# DownLink_ver1.net
KiCad netlist of a schematic drawn in EAGLE
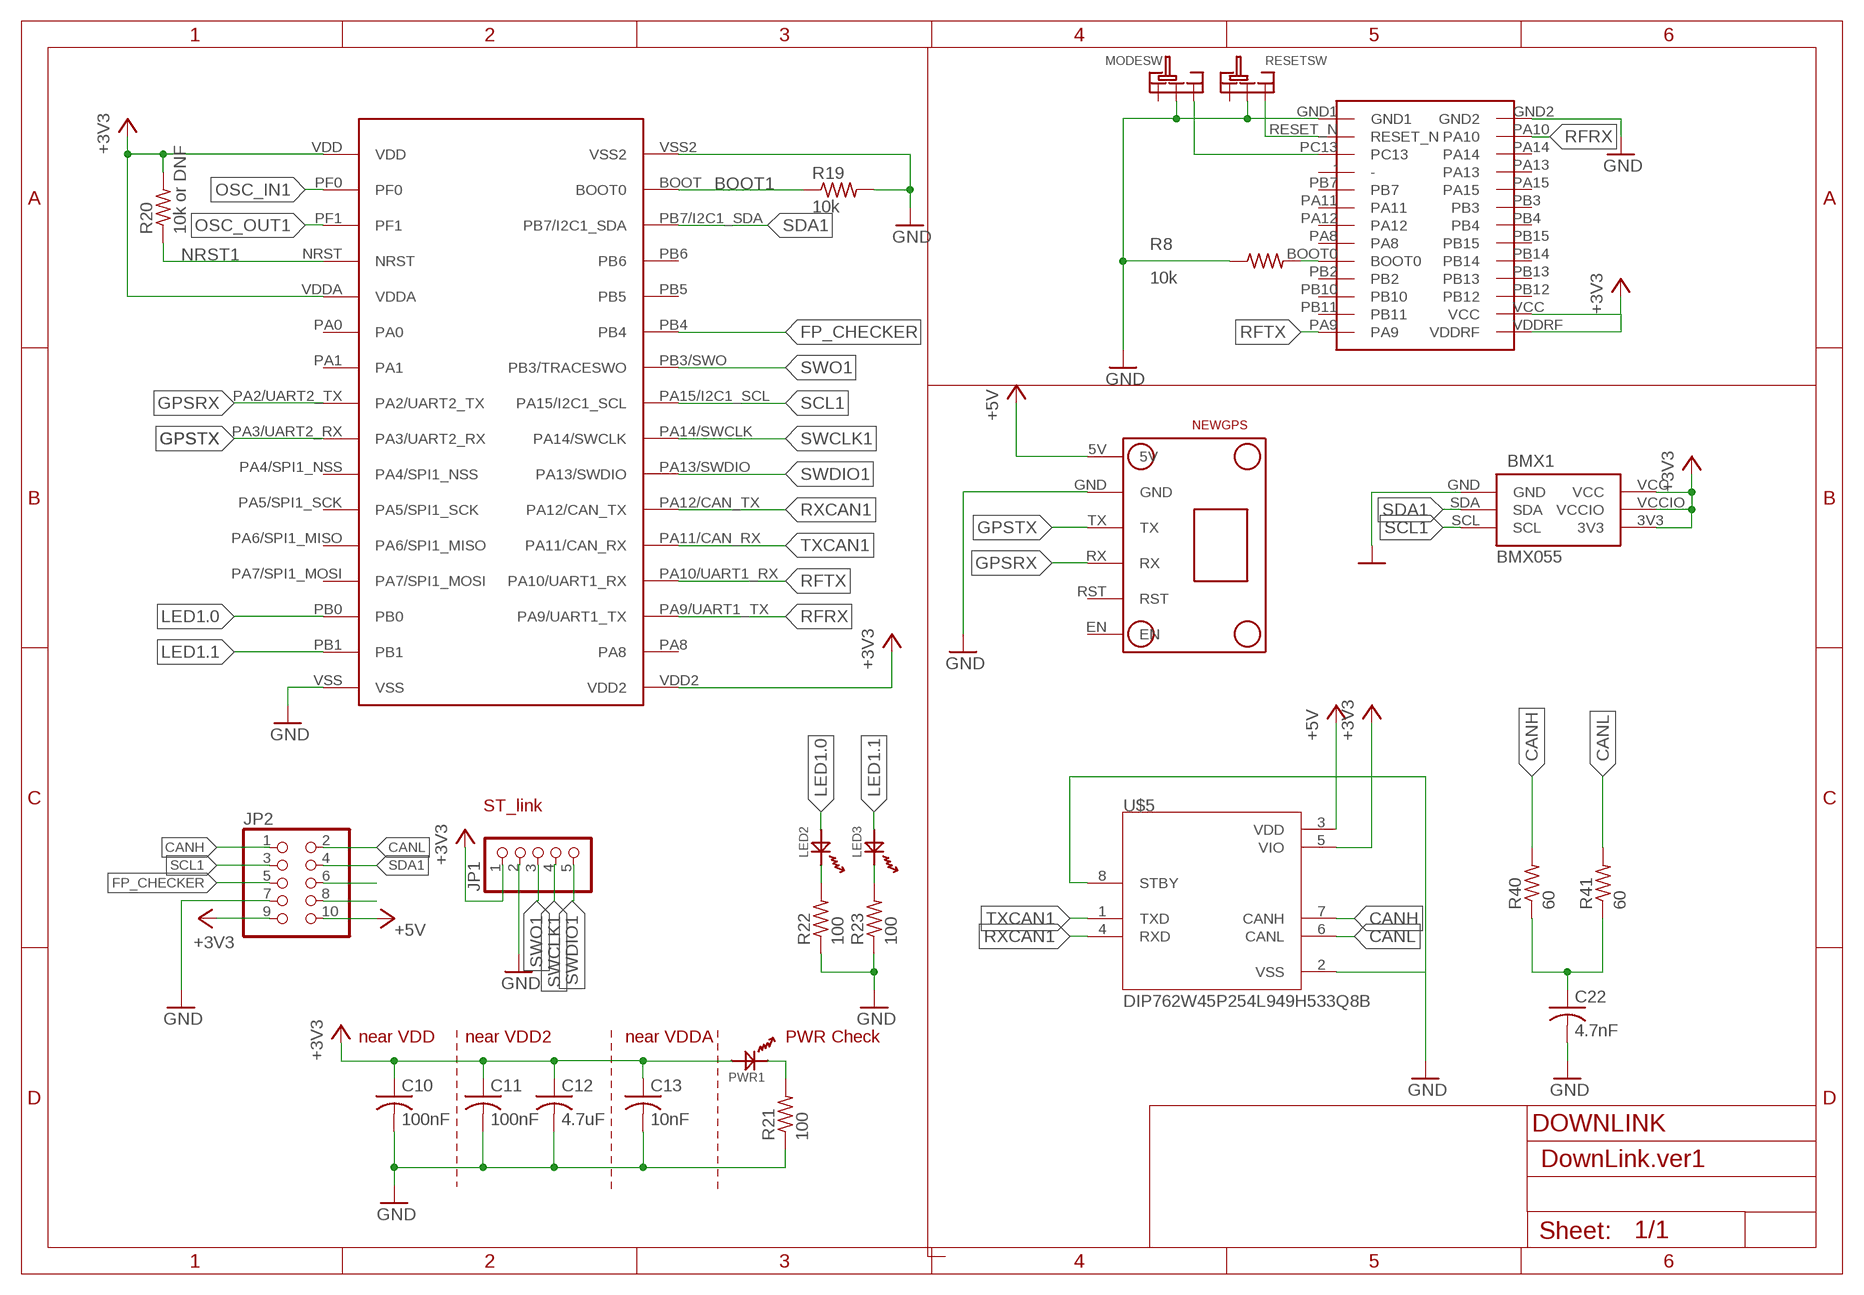
[diagram p0: schematic, sheet 1]

(export (version "E")
  (design (tool "Eeschema 10.0.6"))
  (components
    (comp (ref "BMX1")
      (value "BMX055")
      (footprint "eagle-import:BMX055")
      (libsource (lib "eagle-import") (part "BMX055"))
    )
    (comp (ref "C10")
      (value "100nF")
      (footprint "eagle-import:C1608")
      (libsource (lib "eagle-import") (part "C-USC1608"))
    )
    (comp (ref "C11")
      (value "100nF")
      (footprint "eagle-import:C1608")
      (libsource (lib "eagle-import") (part "C-USC1608"))
    )
    (comp (ref "C12")
      (value "4.7uF")
      (footprint "eagle-import:C1608")
      (libsource (lib "eagle-import") (part "C-USC1608"))
    )
    (comp (ref "C13")
      (value "10nF")
      (footprint "eagle-import:C1608")
      (libsource (lib "eagle-import") (part "C-USC1608"))
    )
    (comp (ref "C22")
      (value "4.7nF")
      (footprint "eagle-import:C0603")
      (libsource (lib "eagle-import") (part "C-USC0603"))
    )
    (comp (ref "JP1")
      (value "PINHD-1X5/90")
      (footprint "eagle-import:1X05_90")
      (libsource (lib "eagle-import") (part "PINHD-1X5/90"))
    )
    (comp (ref "JP2")
      (value "PINHD-2X5/90")
      (footprint "eagle-import:2X05_90")
      (libsource (lib "eagle-import") (part "PINHD-2X5/90"))
    )
    (comp (ref "LED2")
      (value "OSXX1608C1A")
      (footprint "eagle-import:OSXX1608C1A")
      (libsource (lib "eagle-import") (part "OSXX1608C1A"))
    )
    (comp (ref "LED3")
      (value "OSXX1608C1A")
      (footprint "eagle-import:OSXX1608C1A")
      (libsource (lib "eagle-import") (part "OSXX1608C1A"))
    )
    (comp (ref "MODESW")
      (value "SRIDE_SWITCH")
      (footprint "eagle-import:SRIDE_SWITCH")
      (libsource (lib "eagle-import") (part "SRIDE_SWITCH"))
    )
    (comp (ref "PWR1")
      (value "OSXX1608C1A")
      (footprint "eagle-import:OSXX1608C1A")
      (libsource (lib "eagle-import") (part "OSXX1608C1A"))
    )
    (comp (ref "R8")
      (value "10k")
      (footprint "eagle-import:R0603")
      (libsource (lib "eagle-import") (part "R-US_R0603"))
    )
    (comp (ref "R19")
      (value "10k")
      (footprint "eagle-import:R0603")
      (libsource (lib "eagle-import") (part "R-US_R0603"))
    )
    (comp (ref "R20")
      (value "10k or DNF")
      (footprint "eagle-import:R0603")
      (libsource (lib "eagle-import") (part "R-US_R0603"))
    )
    (comp (ref "R21")
      (value "100")
      (footprint "eagle-import:R0603")
      (libsource (lib "eagle-import") (part "R-US_R0603"))
    )
    (comp (ref "R22")
      (value "100")
      (footprint "eagle-import:R0603")
      (libsource (lib "eagle-import") (part "R-US_R0603"))
    )
    (comp (ref "R23")
      (value "100")
      (footprint "eagle-import:R0603")
      (libsource (lib "eagle-import") (part "R-US_R0603"))
    )
    (comp (ref "R40")
      (value "60")
      (footprint "eagle-import:R0603")
      (libsource (lib "eagle-import") (part "R-US_R0603"))
    )
    (comp (ref "R41")
      (value "60")
      (footprint "eagle-import:R0603")
      (libsource (lib "eagle-import") (part "R-US_R0603"))
    )
    (comp (ref "RESETSW")
      (value "SRIDE_SWITCH")
      (footprint "eagle-import:SRIDE_SWITCH")
      (libsource (lib "eagle-import") (part "SRIDE_SWITCH"))
    )
    (comp (ref "STM1")
      (value "STM32F303K8")
      (footprint "eagle-import:STM32F303K8")
      (libsource (lib "eagle-import") (part "STM32F303K8"))
    )
    (comp (ref "U$1")
      (value "NEWGPS")
      (footprint "eagle-import:NEWGPS")
      (libsource (lib "eagle-import") (part "NEWGPS"))
    )
    (comp (ref "U$3")
      (value "RM-92A")
      (footprint "eagle-import:RM-92A")
      (libsource (lib "eagle-import") (part "RM-92A"))
    )
    (comp (ref "U$5")
      (value "DIP762W45P254L949H533Q8B")
      (footprint "eagle-import:DIP762W45P254L949H533Q8B")
      (libsource (lib "eagle-import") (part "DIP762W45P254L949H533Q8B"))
    )
  )
  (nets
    (net (code "1") (name "+3V3") (class "Default")
      (node (ref "BMX1") (pin "3V3") (pinfunction "3V3_3V3") (pintype "power_in"))
      (node (ref "BMX1") (pin "VCC") (pinfunction "VCC_VCC") (pintype "power_in"))
      (node (ref "BMX1") (pin "VCCIO") (pinfunction "VCCIO_VCCIO") (pintype "power_in"))
      (node (ref "C10") (pin "1") (pinfunction "1_1") (pintype "passive"))
      (node (ref "C11") (pin "1") (pinfunction "1_1") (pintype "passive"))
      (node (ref "C12") (pin "1") (pinfunction "1_1") (pintype "passive"))
      (node (ref "C13") (pin "1") (pinfunction "1_1") (pintype "passive"))
      (node (ref "JP1") (pin "1") (pinfunction "1_1") (pintype "passive"))
      (node (ref "JP2") (pin "9") (pinfunction "9_9") (pintype "passive"))
      (node (ref "PWR1") (pin "AN") (pinfunction "AN_AN") (pintype "bidirectional"))
      (node (ref "R20") (pin "2") (pinfunction "2_2") (pintype "passive"))
      (node (ref "STM1") (pin "VDD") (pinfunction "VDD_VDD") (pintype "power_in"))
      (node (ref "STM1") (pin "VDD2") (pinfunction "VDD2_VDD2") (pintype "power_in"))
      (node (ref "STM1") (pin "VDDA") (pinfunction "VDDA_VDDA") (pintype "power_in"))
      (node (ref "U$3") (pin "VCC") (pinfunction "VCC_VCC") (pintype "bidirectional"))
      (node (ref "U$3") (pin "VDDRF") (pinfunction "VDDRF_VDDRF") (pintype "bidirectional"))
      (node (ref "U$5") (pin "5") (pinfunction "VIO_5") (pintype "power_in"))
    )
    (net (code "2") (name "+5V") (class "Default")
      (node (ref "JP2") (pin "10") (pinfunction "10_10") (pintype "passive"))
      (node (ref "U$1") (pin "5V") (pinfunction "5V_5V") (pintype "bidirectional"))
      (node (ref "U$5") (pin "3") (pinfunction "VDD_3") (pintype "power_in"))
    )
    (net (code "3") (name "/BOOT1") (class "Default")
      (node (ref "R19") (pin "1") (pinfunction "1_1") (pintype "passive"))
      (node (ref "STM1") (pin "BOOT") (pinfunction "BOOT0_BOOT") (pintype "bidirectional"))
    )
    (net (code "4") (name "/NRST1") (class "Default")
      (node (ref "R20") (pin "1") (pinfunction "1_1") (pintype "passive"))
      (node (ref "STM1") (pin "NRST") (pinfunction "NRST_NRST") (pintype "bidirectional"))
    )
    (net (code "5") (name "CANH") (class "Default")
      (node (ref "JP2") (pin "1") (pinfunction "1_1") (pintype "passive"))
      (node (ref "R40") (pin "2") (pinfunction "2_2") (pintype "passive"))
      (node (ref "U$5") (pin "7") (pinfunction "CANH_7") (pintype "bidirectional"))
    )
    (net (code "6") (name "CANL") (class "Default")
      (node (ref "JP2") (pin "2") (pinfunction "2_2") (pintype "passive"))
      (node (ref "R41") (pin "2") (pinfunction "2_2") (pintype "passive"))
      (node (ref "U$5") (pin "6") (pinfunction "CANL_6") (pintype "bidirectional"))
    )
    (net (code "7") (name "FP_CHECKER") (class "Default")
      (node (ref "JP2") (pin "5") (pinfunction "5_5") (pintype "passive"))
      (node (ref "STM1") (pin "PB4") (pinfunction "PB4_PB4") (pintype "bidirectional"))
    )
    (net (code "8") (name "GND") (class "Default")
      (node (ref "BMX1") (pin "GND") (pinfunction "GND_GND") (pintype "power_in"))
      (node (ref "C10") (pin "2") (pinfunction "2_2") (pintype "passive"))
      (node (ref "C11") (pin "2") (pinfunction "2_2") (pintype "passive"))
      (node (ref "C12") (pin "2") (pinfunction "2_2") (pintype "passive"))
      (node (ref "C13") (pin "2") (pinfunction "2_2") (pintype "passive"))
      (node (ref "C22") (pin "2") (pinfunction "2_2") (pintype "passive"))
      (node (ref "JP1") (pin "2") (pinfunction "2_2") (pintype "passive"))
      (node (ref "JP2") (pin "7") (pinfunction "7_7") (pintype "passive"))
      (node (ref "MODESW") (pin "LR") (pinfunction "LR_LR") (pintype "bidirectional"))
      (node (ref "R19") (pin "2") (pinfunction "2_2") (pintype "passive"))
      (node (ref "R21") (pin "1") (pinfunction "1_1") (pintype "passive"))
      (node (ref "R22") (pin "1") (pinfunction "1_1") (pintype "passive"))
      (node (ref "R23") (pin "1") (pinfunction "1_1") (pintype "passive"))
      (node (ref "R8") (pin "1") (pinfunction "1_1") (pintype "passive"))
      (node (ref "RESETSW") (pin "LR") (pinfunction "LR_LR") (pintype "bidirectional"))
      (node (ref "STM1") (pin "VSS") (pinfunction "VSS_VSS") (pintype "power_in"))
      (node (ref "STM1") (pin "VSS2") (pinfunction "VSS2_VSS2") (pintype "power_in"))
      (node (ref "U$1") (pin "GND") (pinfunction "GND_GND") (pintype "bidirectional"))
      (node (ref "U$3") (pin "GND1") (pinfunction "GND1_GND1") (pintype "bidirectional"))
      (node (ref "U$3") (pin "GND2") (pinfunction "GND2_GND2") (pintype "bidirectional"))
      (node (ref "U$5") (pin "2") (pinfunction "VSS_2") (pintype "power_in"))
      (node (ref "U$5") (pin "8") (pinfunction "STBY_8") (pintype "input"))
    )
    (net (code "9") (name "GPSRX") (class "Default")
      (node (ref "STM1") (pin "PA2/UART2_TX") (pinfunction "PA2/UART2_TX_PA2/UART2_TX") (pintype "bidirectional"))
      (node (ref "U$1") (pin "RX") (pinfunction "RX_RX") (pintype "bidirectional"))
    )
    (net (code "10") (name "GPSTX") (class "Default")
      (node (ref "STM1") (pin "PA3/UART2_RX") (pinfunction "PA3/UART2_RX_PA3/UART2_RX") (pintype "bidirectional"))
      (node (ref "U$1") (pin "TX") (pinfunction "TX_TX") (pintype "bidirectional"))
    )
    (net (code "11") (name "LED1.0") (class "Default")
      (node (ref "LED2") (pin "AN") (pinfunction "AN_AN") (pintype "bidirectional"))
      (node (ref "STM1") (pin "PB0") (pinfunction "PB0_PB0") (pintype "bidirectional"))
    )
    (net (code "12") (name "LED1.1") (class "Default")
      (node (ref "LED3") (pin "AN") (pinfunction "AN_AN") (pintype "bidirectional"))
      (node (ref "STM1") (pin "PB1") (pinfunction "PB1_PB1") (pintype "bidirectional"))
    )
    (net (code "13") (name "Net-(C22-Pad1)") (class "Default")
      (node (ref "C22") (pin "1") (pinfunction "1_1") (pintype "passive"))
      (node (ref "R40") (pin "1") (pinfunction "1_1") (pintype "passive"))
      (node (ref "R41") (pin "1") (pinfunction "1_1") (pintype "passive"))
    )
    (net (code "14") (name "Net-(LED2-PadCT)") (class "Default")
      (node (ref "LED2") (pin "CT") (pinfunction "CT_CT") (pintype "bidirectional"))
      (node (ref "R22") (pin "2") (pinfunction "2_2") (pintype "passive"))
    )
    (net (code "15") (name "Net-(LED3-PadCT)") (class "Default")
      (node (ref "LED3") (pin "CT") (pinfunction "CT_CT") (pintype "bidirectional"))
      (node (ref "R23") (pin "2") (pinfunction "2_2") (pintype "passive"))
    )
    (net (code "16") (name "Net-(MODESW-PadR)") (class "Default")
      (node (ref "MODESW") (pin "R") (pinfunction "R_R") (pintype "bidirectional"))
      (node (ref "U$3") (pin "PC13") (pinfunction "PC13_PC13") (pintype "bidirectional"))
    )
    (net (code "17") (name "Net-(PWR1-PadCT)") (class "Default")
      (node (ref "PWR1") (pin "CT") (pinfunction "CT_CT") (pintype "bidirectional"))
      (node (ref "R21") (pin "2") (pinfunction "2_2") (pintype "passive"))
    )
    (net (code "18") (name "Net-(R8-Pad2)") (class "Default")
      (node (ref "R8") (pin "2") (pinfunction "2_2") (pintype "passive"))
      (node (ref "U$3") (pin "BOOT0") (pinfunction "BOOT0_BOOT0") (pintype "bidirectional"))
    )
    (net (code "19") (name "Net-(RESETSW-PadR)") (class "Default")
      (node (ref "RESETSW") (pin "R") (pinfunction "R_R") (pintype "bidirectional"))
      (node (ref "U$3") (pin "RESET_N") (pinfunction "RESET_N_RESET_N") (pintype "bidirectional"))
    )
    (net (code "20") (name "OSC_IN1") (class "Default")
      (node (ref "STM1") (pin "PF0") (pinfunction "PF0_PF0") (pintype "bidirectional"))
    )
    (net (code "21") (name "OSC_OUT1") (class "Default")
      (node (ref "STM1") (pin "PF1") (pinfunction "PF1_PF1") (pintype "bidirectional"))
    )
    (net (code "22") (name "RFRX") (class "Default")
      (node (ref "STM1") (pin "PA9/UART1_TX") (pinfunction "PA9/UART1_TX_PA9/UART1_TX") (pintype "bidirectional"))
      (node (ref "U$3") (pin "PA10") (pinfunction "PA10_PA10") (pintype "bidirectional"))
    )
    (net (code "23") (name "RFTX") (class "Default")
      (node (ref "STM1") (pin "PA10/UART1_RX") (pinfunction "PA10/UART1_RX_PA10/UART1_RX") (pintype "bidirectional"))
      (node (ref "U$3") (pin "PA9") (pinfunction "PA9_PA9") (pintype "bidirectional"))
    )
    (net (code "24") (name "RXCAN1") (class "Default")
      (node (ref "STM1") (pin "PA12/CAN_TX") (pinfunction "PA12/CAN_TX_PA12/CAN_TX") (pintype "bidirectional"))
      (node (ref "U$5") (pin "4") (pinfunction "RXD_4") (pintype "output"))
    )
    (net (code "25") (name "SCL1") (class "Default")
      (node (ref "BMX1") (pin "SCL") (pinfunction "SCL_SCL") (pintype "bidirectional"))
      (node (ref "JP2") (pin "3") (pinfunction "3_3") (pintype "passive"))
      (node (ref "STM1") (pin "PA15/I2C1_SCL") (pinfunction "PA15/I2C1_SCL_PA15/I2C1_SCL") (pintype "bidirectional"))
    )
    (net (code "26") (name "SDA1") (class "Default")
      (node (ref "BMX1") (pin "SDA") (pinfunction "SDA_SDA") (pintype "bidirectional"))
      (node (ref "JP2") (pin "4") (pinfunction "4_4") (pintype "passive"))
      (node (ref "STM1") (pin "PB7/I2C1_SDA") (pinfunction "PB7/I2C1_SDA_PB7/I2C1_SDA") (pintype "bidirectional"))
    )
    (net (code "27") (name "SWCLK1") (class "Default")
      (node (ref "JP1") (pin "4") (pinfunction "4_4") (pintype "passive"))
      (node (ref "STM1") (pin "PA14/SWCLK") (pinfunction "PA14/SWCLK_PA14/SWCLK") (pintype "bidirectional"))
    )
    (net (code "28") (name "SWDIO1") (class "Default")
      (node (ref "JP1") (pin "5") (pinfunction "5_5") (pintype "passive"))
      (node (ref "STM1") (pin "PA13/SWDIO") (pinfunction "PA13/SWDIO_PA13/SWDIO") (pintype "bidirectional"))
    )
    (net (code "29") (name "SWO1") (class "Default")
      (node (ref "JP1") (pin "3") (pinfunction "3_3") (pintype "passive"))
      (node (ref "STM1") (pin "PB3/SWO") (pinfunction "PB3/TRACESWO_PB3/SWO") (pintype "bidirectional"))
    )
    (net (code "30") (name "TXCAN1") (class "Default")
      (node (ref "STM1") (pin "PA11/CAN_RX") (pinfunction "PA11/CAN_RX_PA11/CAN_RX") (pintype "bidirectional"))
      (node (ref "U$5") (pin "1") (pinfunction "TXD_1") (pintype "input"))
    )
    (net (code "31") (name "unconnected-(JP2-Pad6)") (class "Default")
      (node (ref "JP2") (pin "6") (pinfunction "6_6") (pintype "passive"))
    )
    (net (code "32") (name "unconnected-(JP2-Pad8)") (class "Default")
      (node (ref "JP2") (pin "8") (pinfunction "8_8") (pintype "passive"))
    )
    (net (code "33") (name "unconnected-(MODESW-PadL)") (class "Default")
      (node (ref "MODESW") (pin "L") (pinfunction "L_L") (pintype "bidirectional"))
    )
    (net (code "34") (name "unconnected-(RESETSW-PadL)") (class "Default")
      (node (ref "RESETSW") (pin "L") (pinfunction "L_L") (pintype "bidirectional"))
    )
    (net (code "35") (name "unconnected-(STM1-PadPA0)") (class "Default")
      (node (ref "STM1") (pin "PA0") (pinfunction "PA0_PA0") (pintype "bidirectional"))
    )
    (net (code "36") (name "unconnected-(STM1-PadPA1)") (class "Default")
      (node (ref "STM1") (pin "PA1") (pinfunction "PA1_PA1") (pintype "bidirectional"))
    )
    (net (code "37") (name "unconnected-(STM1-PadPA4{slash}SPI1_NSS)") (class "Default")
      (node (ref "STM1") (pin "PA4/SPI1_NSS") (pinfunction "PA4/SPI1_NSS_PA4/SPI1_NSS") (pintype "bidirectional"))
    )
    (net (code "38") (name "unconnected-(STM1-PadPA5{slash}SPI1_SCK)") (class "Default")
      (node (ref "STM1") (pin "PA5/SPI1_SCK") (pinfunction "PA5/SPI1_SCK_PA5/SPI1_SCK") (pintype "bidirectional"))
    )
    (net (code "39") (name "unconnected-(STM1-PadPA6{slash}SPI1_MISO)") (class "Default")
      (node (ref "STM1") (pin "PA6/SPI1_MISO") (pinfunction "PA6/SPI1_MISO_PA6/SPI1_MISO") (pintype "bidirectional"))
    )
    (net (code "40") (name "unconnected-(STM1-PadPA7{slash}SPI1_MOSI)") (class "Default")
      (node (ref "STM1") (pin "PA7/SPI1_MOSI") (pinfunction "PA7/SPI1_MOSI_PA7/SPI1_MOSI") (pintype "bidirectional"))
    )
    (net (code "41") (name "unconnected-(STM1-PadPA8)") (class "Default")
      (node (ref "STM1") (pin "PA8") (pinfunction "PA8_PA8") (pintype "bidirectional"))
    )
    (net (code "42") (name "unconnected-(STM1-PadPB5)") (class "Default")
      (node (ref "STM1") (pin "PB5") (pinfunction "PB5_PB5") (pintype "bidirectional"))
    )
    (net (code "43") (name "unconnected-(STM1-PadPB6)") (class "Default")
      (node (ref "STM1") (pin "PB6") (pinfunction "PB6_PB6") (pintype "bidirectional"))
    )
    (net (code "44") (name "unconnected-(U$1-PadEN)") (class "Default")
      (node (ref "U$1") (pin "EN") (pinfunction "EN_EN") (pintype "bidirectional"))
    )
    (net (code "45") (name "unconnected-(U$1-PadRST)") (class "Default")
      (node (ref "U$1") (pin "RST") (pinfunction "RST_RST") (pintype "bidirectional"))
    )
    (net (code "46") (name "unconnected-(U$3-Pad-)") (class "Default")
      (node (ref "U$3") (pin "-") (pinfunction "-_-") (pintype "bidirectional"))
    )
    (net (code "47") (name "unconnected-(U$3-PadPA8)") (class "Default")
      (node (ref "U$3") (pin "PA8") (pinfunction "PA8_PA8") (pintype "bidirectional"))
    )
    (net (code "48") (name "unconnected-(U$3-PadPA11)") (class "Default")
      (node (ref "U$3") (pin "PA11") (pinfunction "PA11_PA11") (pintype "bidirectional"))
    )
    (net (code "49") (name "unconnected-(U$3-PadPA12)") (class "Default")
      (node (ref "U$3") (pin "PA12") (pinfunction "PA12_PA12") (pintype "bidirectional"))
    )
    (net (code "50") (name "unconnected-(U$3-PadPA13)") (class "Default")
      (node (ref "U$3") (pin "PA13") (pinfunction "PA13_PA13") (pintype "bidirectional"))
    )
    (net (code "51") (name "unconnected-(U$3-PadPA14)") (class "Default")
      (node (ref "U$3") (pin "PA14") (pinfunction "PA14_PA14") (pintype "bidirectional"))
    )
    (net (code "52") (name "unconnected-(U$3-PadPA15)") (class "Default")
      (node (ref "U$3") (pin "PA15") (pinfunction "PA15_PA15") (pintype "bidirectional"))
    )
    (net (code "53") (name "unconnected-(U$3-PadPB2)") (class "Default")
      (node (ref "U$3") (pin "PB2") (pinfunction "PB2_PB2") (pintype "bidirectional"))
    )
    (net (code "54") (name "unconnected-(U$3-PadPB3)") (class "Default")
      (node (ref "U$3") (pin "PB3") (pinfunction "PB3_PB3") (pintype "bidirectional"))
    )
    (net (code "55") (name "unconnected-(U$3-PadPB4)") (class "Default")
      (node (ref "U$3") (pin "PB4") (pinfunction "PB4_PB4") (pintype "bidirectional"))
    )
    (net (code "56") (name "unconnected-(U$3-PadPB7)") (class "Default")
      (node (ref "U$3") (pin "PB7") (pinfunction "PB7_PB7") (pintype "bidirectional"))
    )
    (net (code "57") (name "unconnected-(U$3-PadPB10)") (class "Default")
      (node (ref "U$3") (pin "PB10") (pinfunction "PB10_PB10") (pintype "bidirectional"))
    )
    (net (code "58") (name "unconnected-(U$3-PadPB11)") (class "Default")
      (node (ref "U$3") (pin "PB11") (pinfunction "PB11_PB11") (pintype "bidirectional"))
    )
    (net (code "59") (name "unconnected-(U$3-PadPB12)") (class "Default")
      (node (ref "U$3") (pin "PB12") (pinfunction "PB12_PB12") (pintype "bidirectional"))
    )
    (net (code "60") (name "unconnected-(U$3-PadPB13)") (class "Default")
      (node (ref "U$3") (pin "PB13") (pinfunction "PB13_PB13") (pintype "bidirectional"))
    )
    (net (code "61") (name "unconnected-(U$3-PadPB14)") (class "Default")
      (node (ref "U$3") (pin "PB14") (pinfunction "PB14_PB14") (pintype "bidirectional"))
    )
    (net (code "62") (name "unconnected-(U$3-PadPB15)") (class "Default")
      (node (ref "U$3") (pin "PB15") (pinfunction "PB15_PB15") (pintype "bidirectional"))
    )
  )
)
